# init_test_hall.net
KiCad netlist of a schematic drawn in EAGLE
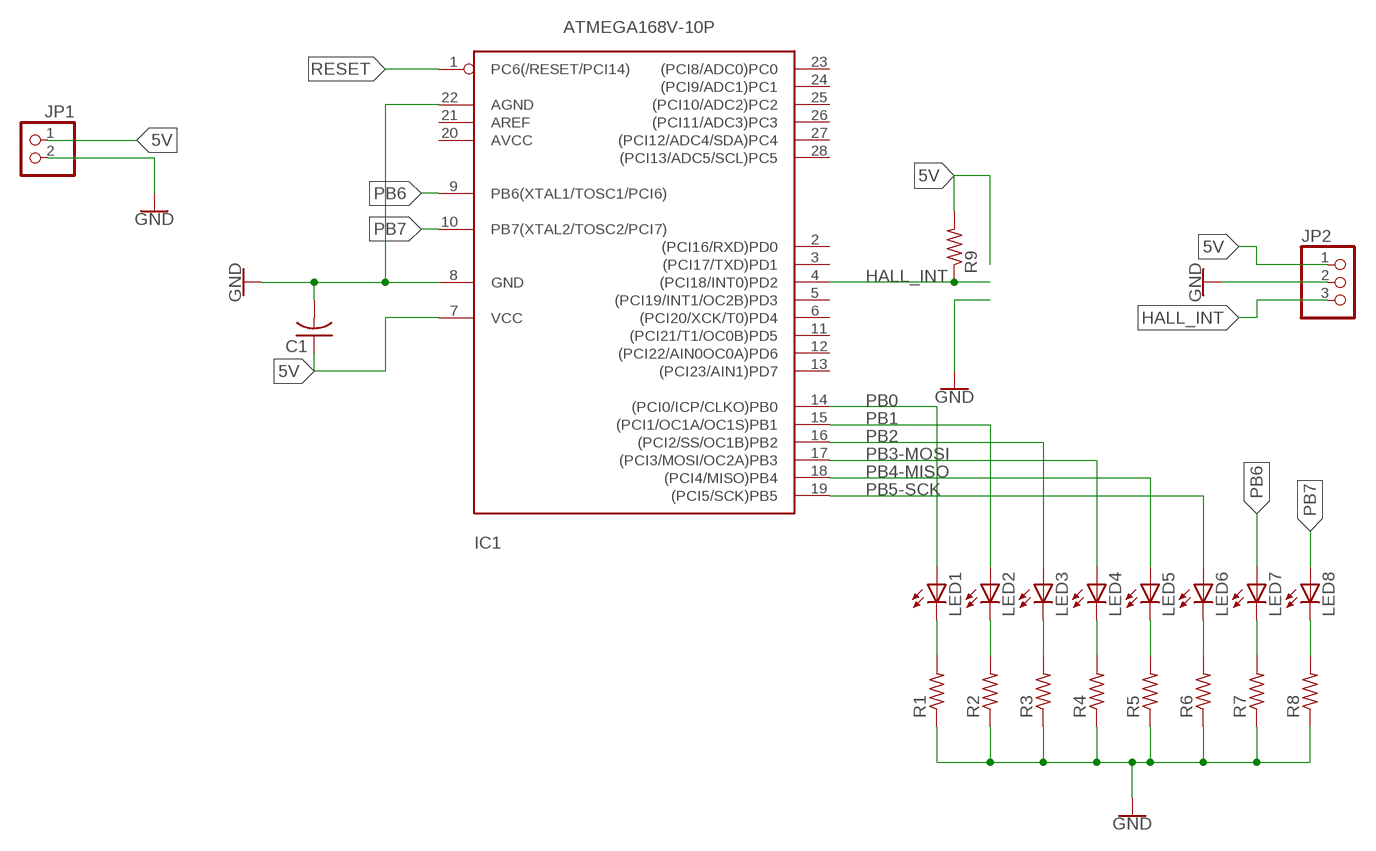
[diagram p0: schematic, sheet 1]

(export (version "E")
  (design (tool "Eeschema 10.0.6"))
  (components
    (comp (ref "C1")
      (value "C-US025-030X050")
      (footprint "eagle-import:C025-030X050")
      (libsource (lib "eagle-import") (part "C-US025-030X050"))
    )
    (comp (ref "IC1")
      (value "ATMEGA168V-10P")
      (footprint "eagle-import:DIL28-3")
      (libsource (lib "eagle-import") (part "ATMEGA168PV-10"))
    )
    (comp (ref "JP1")
      (value "PINHD-1X2")
      (footprint "eagle-import:1X02")
      (libsource (lib "eagle-import") (part "PINHD-1X2"))
    )
    (comp (ref "JP2")
      (value "PINHD-1X3")
      (footprint "eagle-import:1X03")
      (libsource (lib "eagle-import") (part "PINHD-1X3"))
    )
    (comp (ref "LED1")
      (value "LED3MM")
      (footprint "eagle-import:LED3MM")
      (libsource (lib "eagle-import") (part "LED3MM"))
    )
    (comp (ref "LED2")
      (value "LED3MM")
      (footprint "eagle-import:LED3MM")
      (libsource (lib "eagle-import") (part "LED3MM"))
    )
    (comp (ref "LED3")
      (value "LED3MM")
      (footprint "eagle-import:LED3MM")
      (libsource (lib "eagle-import") (part "LED3MM"))
    )
    (comp (ref "LED4")
      (value "LED3MM")
      (footprint "eagle-import:LED3MM")
      (libsource (lib "eagle-import") (part "LED3MM"))
    )
    (comp (ref "LED5")
      (value "LED3MM")
      (footprint "eagle-import:LED3MM")
      (libsource (lib "eagle-import") (part "LED3MM"))
    )
    (comp (ref "LED6")
      (value "LED3MM")
      (footprint "eagle-import:LED3MM")
      (libsource (lib "eagle-import") (part "LED3MM"))
    )
    (comp (ref "LED7")
      (value "LED3MM")
      (footprint "eagle-import:LED3MM")
      (libsource (lib "eagle-import") (part "LED3MM"))
    )
    (comp (ref "LED8")
      (value "LED3MM")
      (footprint "eagle-import:LED3MM")
      (libsource (lib "eagle-import") (part "LED3MM"))
    )
    (comp (ref "R1")
      (value "R-US_0207/7")
      (footprint "eagle-import:0207_7")
      (libsource (lib "eagle-import") (part "R-US_0207/7"))
    )
    (comp (ref "R2")
      (value "R-US_0207/7")
      (footprint "eagle-import:0207_7")
      (libsource (lib "eagle-import") (part "R-US_0207/7"))
    )
    (comp (ref "R3")
      (value "R-US_0207/7")
      (footprint "eagle-import:0207_7")
      (libsource (lib "eagle-import") (part "R-US_0207/7"))
    )
    (comp (ref "R4")
      (value "R-US_0207/7")
      (footprint "eagle-import:0207_7")
      (libsource (lib "eagle-import") (part "R-US_0207/7"))
    )
    (comp (ref "R5")
      (value "R-US_0207/7")
      (footprint "eagle-import:0207_7")
      (libsource (lib "eagle-import") (part "R-US_0207/7"))
    )
    (comp (ref "R6")
      (value "R-US_0207/7")
      (footprint "eagle-import:0207_7")
      (libsource (lib "eagle-import") (part "R-US_0207/7"))
    )
    (comp (ref "R7")
      (value "R-US_0207/7")
      (footprint "eagle-import:0207_7")
      (libsource (lib "eagle-import") (part "R-US_0207/7"))
    )
    (comp (ref "R8")
      (value "R-US_0207/7")
      (footprint "eagle-import:0207_7")
      (libsource (lib "eagle-import") (part "R-US_0207/7"))
    )
    (comp (ref "R9")
      (value "R-US_0207/7")
      (footprint "eagle-import:0207_7")
      (libsource (lib "eagle-import") (part "R-US_0207/7"))
    )
  )
  (nets
    (net (code "1") (name "/PB0") (class "Default")
      (node (ref "IC1") (pin "14") (pinfunction "(PCI0/ICP/CLKO)PB0_14") (pintype "bidirectional"))
      (node (ref "LED1") (pin "A") (pinfunction "A_A") (pintype "passive"))
    )
    (net (code "2") (name "/PB1") (class "Default")
      (node (ref "IC1") (pin "15") (pinfunction "(PCI1/OC1A/OC1S)PB1_15") (pintype "bidirectional"))
      (node (ref "LED2") (pin "A") (pinfunction "A_A") (pintype "passive"))
    )
    (net (code "3") (name "/PB2") (class "Default")
      (node (ref "IC1") (pin "16") (pinfunction "(PCI2/SS/OC1B)PB2_16") (pintype "bidirectional"))
      (node (ref "LED3") (pin "A") (pinfunction "A_A") (pintype "passive"))
    )
    (net (code "4") (name "/PB3-MOSI") (class "Default")
      (node (ref "IC1") (pin "17") (pinfunction "(PCI3/MOSI/OC2A)PB3_17") (pintype "bidirectional"))
      (node (ref "LED4") (pin "A") (pinfunction "A_A") (pintype "passive"))
    )
    (net (code "5") (name "/PB4-MISO") (class "Default")
      (node (ref "IC1") (pin "18") (pinfunction "(PCI4/MISO)PB4_18") (pintype "bidirectional"))
      (node (ref "LED5") (pin "A") (pinfunction "A_A") (pintype "passive"))
    )
    (net (code "6") (name "/PB5-SCK") (class "Default")
      (node (ref "IC1") (pin "19") (pinfunction "(PCI5/SCK)PB5_19") (pintype "bidirectional"))
      (node (ref "LED6") (pin "A") (pinfunction "A_A") (pintype "passive"))
    )
    (net (code "7") (name "5V") (class "Default")
      (node (ref "C1") (pin "1") (pinfunction "1_1") (pintype "passive"))
      (node (ref "IC1") (pin "7") (pinfunction "VCC_7") (pintype "bidirectional"))
      (node (ref "JP1") (pin "1") (pinfunction "1_1") (pintype "passive"))
      (node (ref "JP2") (pin "1") (pinfunction "1_1") (pintype "passive"))
      (node (ref "R9") (pin "2") (pinfunction "2_2") (pintype "passive"))
    )
    (net (code "8") (name "GND") (class "Default")
      (node (ref "C1") (pin "2") (pinfunction "2_2") (pintype "passive"))
      (node (ref "IC1") (pin "22") (pinfunction "AGND_22") (pintype "bidirectional"))
      (node (ref "IC1") (pin "8") (pinfunction "GND_8") (pintype "bidirectional"))
      (node (ref "JP1") (pin "2") (pinfunction "2_2") (pintype "passive"))
      (node (ref "JP2") (pin "2") (pinfunction "2_2") (pintype "passive"))
      (node (ref "R1") (pin "1") (pinfunction "1_1") (pintype "passive"))
      (node (ref "R2") (pin "1") (pinfunction "1_1") (pintype "passive"))
      (node (ref "R3") (pin "1") (pinfunction "1_1") (pintype "passive"))
      (node (ref "R4") (pin "1") (pinfunction "1_1") (pintype "passive"))
      (node (ref "R5") (pin "1") (pinfunction "1_1") (pintype "passive"))
      (node (ref "R6") (pin "1") (pinfunction "1_1") (pintype "passive"))
      (node (ref "R7") (pin "1") (pinfunction "1_1") (pintype "passive"))
      (node (ref "R8") (pin "1") (pinfunction "1_1") (pintype "passive"))
    )
    (net (code "9") (name "HALL_INT") (class "Default")
      (node (ref "IC1") (pin "4") (pinfunction "(PCI18/INT0)PD2_4") (pintype "bidirectional"))
      (node (ref "JP2") (pin "3") (pinfunction "3_3") (pintype "passive"))
      (node (ref "R9") (pin "1") (pinfunction "1_1") (pintype "passive"))
    )
    (net (code "10") (name "Net-(LED1-C)") (class "Default")
      (node (ref "LED1") (pin "K") (pinfunction "C_K") (pintype "passive"))
      (node (ref "R1") (pin "2") (pinfunction "2_2") (pintype "passive"))
    )
    (net (code "11") (name "Net-(LED2-C)") (class "Default")
      (node (ref "LED2") (pin "K") (pinfunction "C_K") (pintype "passive"))
      (node (ref "R2") (pin "2") (pinfunction "2_2") (pintype "passive"))
    )
    (net (code "12") (name "Net-(LED3-C)") (class "Default")
      (node (ref "LED3") (pin "K") (pinfunction "C_K") (pintype "passive"))
      (node (ref "R3") (pin "2") (pinfunction "2_2") (pintype "passive"))
    )
    (net (code "13") (name "Net-(LED4-C)") (class "Default")
      (node (ref "LED4") (pin "K") (pinfunction "C_K") (pintype "passive"))
      (node (ref "R4") (pin "2") (pinfunction "2_2") (pintype "passive"))
    )
    (net (code "14") (name "Net-(LED5-C)") (class "Default")
      (node (ref "LED5") (pin "K") (pinfunction "C_K") (pintype "passive"))
      (node (ref "R5") (pin "2") (pinfunction "2_2") (pintype "passive"))
    )
    (net (code "15") (name "Net-(LED6-C)") (class "Default")
      (node (ref "LED6") (pin "K") (pinfunction "C_K") (pintype "passive"))
      (node (ref "R6") (pin "2") (pinfunction "2_2") (pintype "passive"))
    )
    (net (code "16") (name "Net-(LED7-C)") (class "Default")
      (node (ref "LED7") (pin "K") (pinfunction "C_K") (pintype "passive"))
      (node (ref "R7") (pin "2") (pinfunction "2_2") (pintype "passive"))
    )
    (net (code "17") (name "Net-(LED8-C)") (class "Default")
      (node (ref "LED8") (pin "K") (pinfunction "C_K") (pintype "passive"))
      (node (ref "R8") (pin "2") (pinfunction "2_2") (pintype "passive"))
    )
    (net (code "18") (name "PB6") (class "Default")
      (node (ref "IC1") (pin "9") (pinfunction "PB6(XTAL1/TOSC1/PCI6)_9") (pintype "bidirectional"))
      (node (ref "LED7") (pin "A") (pinfunction "A_A") (pintype "passive"))
    )
    (net (code "19") (name "PB7") (class "Default")
      (node (ref "IC1") (pin "10") (pinfunction "PB7(XTAL2/TOSC2/PCI7)_10") (pintype "bidirectional"))
      (node (ref "LED8") (pin "A") (pinfunction "A_A") (pintype "passive"))
    )
    (net (code "20") (name "RESET") (class "Default")
      (node (ref "IC1") (pin "1") (pinfunction "PC6(/RESET/PCI14)_1") (pintype "bidirectional"))
    )
    (net (code "21") (name "unconnected-(IC1-(PCI8{slash}ADC0)PC0-Pad23)") (class "Default")
      (node (ref "IC1") (pin "23") (pinfunction "(PCI8/ADC0)PC0_23") (pintype "bidirectional"))
    )
    (net (code "22") (name "unconnected-(IC1-(PCI9{slash}ADC1)PC1-Pad24)") (class "Default")
      (node (ref "IC1") (pin "24") (pinfunction "(PCI9/ADC1)PC1_24") (pintype "bidirectional"))
    )
    (net (code "23") (name "unconnected-(IC1-(PCI10{slash}ADC2)PC2-Pad25)") (class "Default")
      (node (ref "IC1") (pin "25") (pinfunction "(PCI10/ADC2)PC2_25") (pintype "bidirectional"))
    )
    (net (code "24") (name "unconnected-(IC1-(PCI11{slash}ADC3)PC3-Pad26)") (class "Default")
      (node (ref "IC1") (pin "26") (pinfunction "(PCI11/ADC3)PC3_26") (pintype "bidirectional"))
    )
    (net (code "25") (name "unconnected-(IC1-(PCI12{slash}ADC4{slash}SDA)PC4-Pad27)") (class "Default")
      (node (ref "IC1") (pin "27") (pinfunction "(PCI12/ADC4/SDA)PC4_27") (pintype "bidirectional"))
    )
    (net (code "26") (name "unconnected-(IC1-(PCI13{slash}ADC5{slash}SCL)PC5-Pad28)") (class "Default")
      (node (ref "IC1") (pin "28") (pinfunction "(PCI13/ADC5/SCL)PC5_28") (pintype "bidirectional"))
    )
    (net (code "27") (name "unconnected-(IC1-(PCI16{slash}RXD)PD0-Pad2)") (class "Default")
      (node (ref "IC1") (pin "2") (pinfunction "(PCI16/RXD)PD0_2") (pintype "bidirectional"))
    )
    (net (code "28") (name "unconnected-(IC1-(PCI17{slash}TXD)PD1-Pad3)") (class "Default")
      (node (ref "IC1") (pin "3") (pinfunction "(PCI17/TXD)PD1_3") (pintype "bidirectional"))
    )
    (net (code "29") (name "unconnected-(IC1-(PCI19{slash}INT1{slash}OC2B)PD3-Pad5)") (class "Default")
      (node (ref "IC1") (pin "5") (pinfunction "(PCI19/INT1/OC2B)PD3_5") (pintype "bidirectional"))
    )
    (net (code "30") (name "unconnected-(IC1-(PCI20{slash}XCK{slash}T0)PD4-Pad6)") (class "Default")
      (node (ref "IC1") (pin "6") (pinfunction "(PCI20/XCK/T0)PD4_6") (pintype "bidirectional"))
    )
    (net (code "31") (name "unconnected-(IC1-(PCI21{slash}T1{slash}OC0B)PD5-Pad11)") (class "Default")
      (node (ref "IC1") (pin "11") (pinfunction "(PCI21/T1/OC0B)PD5_11") (pintype "bidirectional"))
    )
    (net (code "32") (name "unconnected-(IC1-(PCI22{slash}AIN0OC0A)PD6-Pad12)") (class "Default")
      (node (ref "IC1") (pin "12") (pinfunction "(PCI22/AIN0OC0A)PD6_12") (pintype "bidirectional"))
    )
    (net (code "33") (name "unconnected-(IC1-(PCI23{slash}AIN1)PD7-Pad13)") (class "Default")
      (node (ref "IC1") (pin "13") (pinfunction "(PCI23/AIN1)PD7_13") (pintype "bidirectional"))
    )
    (net (code "34") (name "unconnected-(IC1-AREF-Pad21)") (class "Default")
      (node (ref "IC1") (pin "21") (pinfunction "AREF_21") (pintype "bidirectional"))
    )
    (net (code "35") (name "unconnected-(IC1-AVCC-Pad20)") (class "Default")
      (node (ref "IC1") (pin "20") (pinfunction "AVCC_20") (pintype "bidirectional"))
    )
  )
)
